# Lagopus_A_2.net
KiCad netlist of a schematic drawn in EAGLE
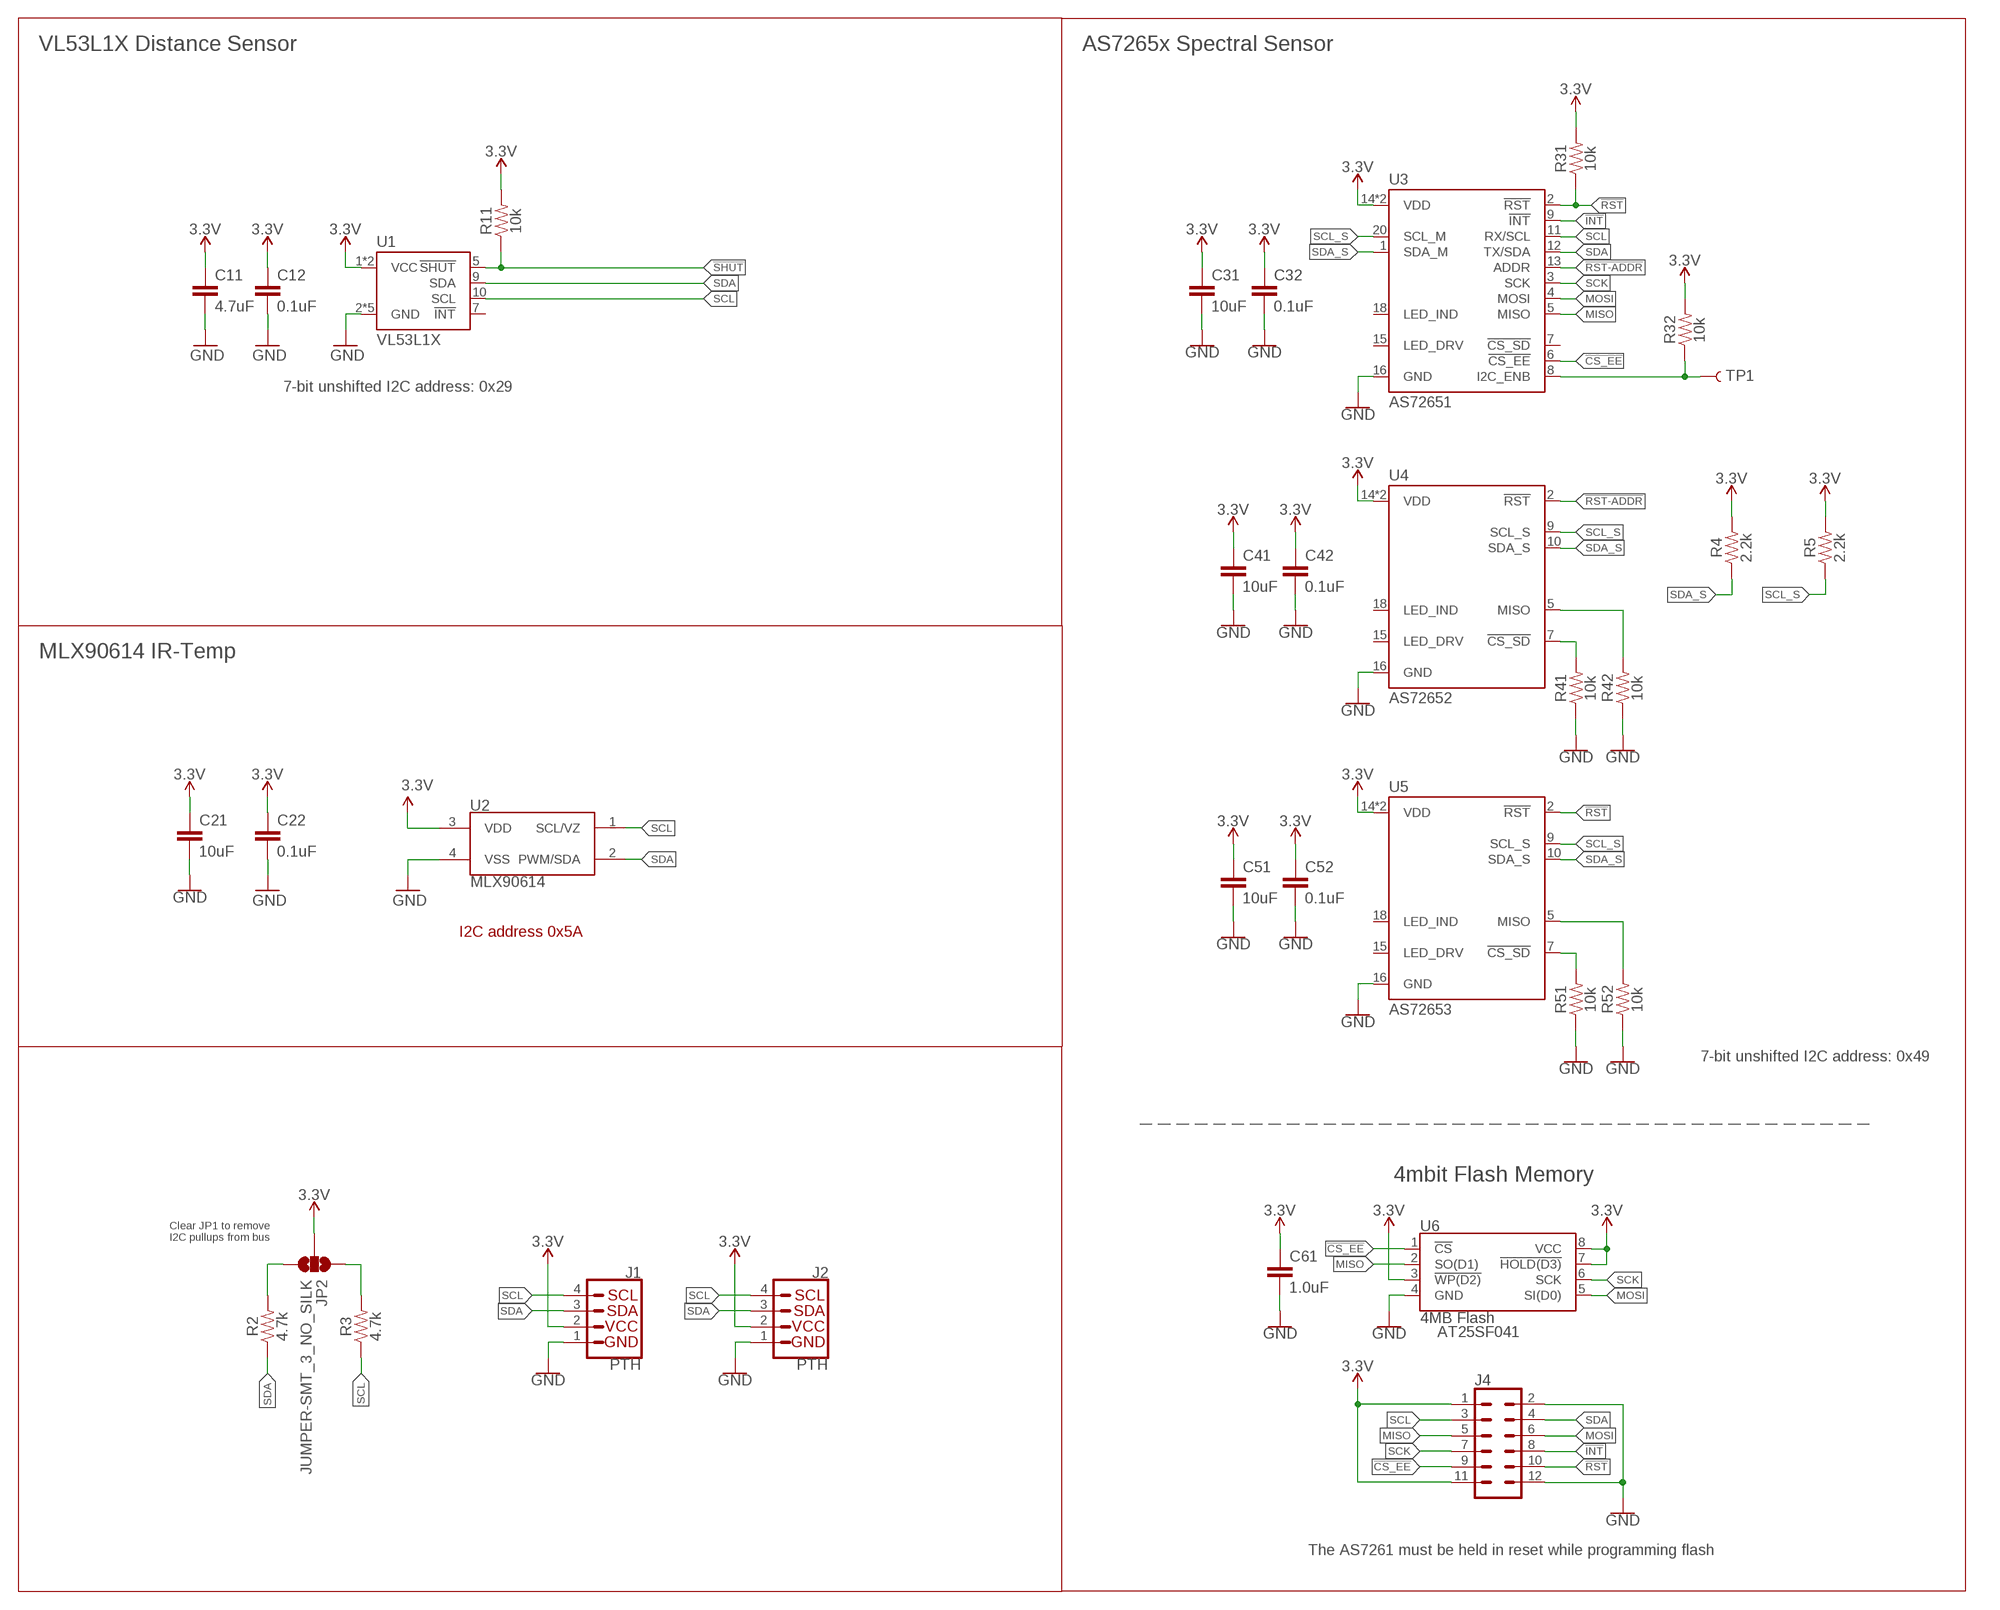
[diagram p0: schematic, sheet 1]

(export (version "E")
  (design (tool "Eeschema 10.0.6"))
  (components
    (comp (ref "C11")
      (value "4.7uF")
      (footprint "eagle-import:0603")
      (libsource (lib "eagle-import") (part "4.7UF0603"))
    )
    (comp (ref "C12")
      (value "0.1uF")
      (footprint "eagle-import:0603")
      (libsource (lib "eagle-import") (part "0.1UF-0603-25V-(+80/-20%)"))
    )
    (comp (ref "C21")
      (value "10uF")
      (footprint "eagle-import:0603")
      (libsource (lib "eagle-import") (part "10UF-0603-6.3V-20%"))
    )
    (comp (ref "C22")
      (value "0.1uF")
      (footprint "eagle-import:0603")
      (libsource (lib "eagle-import") (part "0.1UF-0603-25V-(+80/-20%)"))
    )
    (comp (ref "C31")
      (value "10uF")
      (footprint "eagle-import:0603")
      (libsource (lib "eagle-import") (part "10UF-0603-6.3V-20%"))
    )
    (comp (ref "C32")
      (value "0.1uF")
      (footprint "eagle-import:0603")
      (libsource (lib "eagle-import") (part "0.1UF-0603-25V-(+80/-20%)"))
    )
    (comp (ref "C41")
      (value "10uF")
      (footprint "eagle-import:0603")
      (libsource (lib "eagle-import") (part "10UF-0603-6.3V-20%"))
    )
    (comp (ref "C42")
      (value "0.1uF")
      (footprint "eagle-import:0603")
      (libsource (lib "eagle-import") (part "0.1UF-0603-25V-(+80/-20%)"))
    )
    (comp (ref "C51")
      (value "10uF")
      (footprint "eagle-import:0603")
      (libsource (lib "eagle-import") (part "10UF-0603-6.3V-20%"))
    )
    (comp (ref "C52")
      (value "0.1uF")
      (footprint "eagle-import:0603")
      (libsource (lib "eagle-import") (part "0.1UF-0603-25V-(+80/-20%)"))
    )
    (comp (ref "C61")
      (value "1.0uF")
      (footprint "eagle-import:0603")
      (libsource (lib "eagle-import") (part "1.0UF-0603-16V-10%"))
    )
    (comp (ref "J1")
      (value "PTH")
      (footprint "eagle-import:1X04_NO_SILK")
      (libsource (lib "eagle-import") (part "I2C_STANDARD_NO_SILK"))
    )
    (comp (ref "J2")
      (value "PTH")
      (footprint "eagle-import:1X04_NO_SILK")
      (libsource (lib "eagle-import") (part "I2C_STANDARD_NO_SILK"))
    )
    (comp (ref "J4")
      (value "CONN_06X2SMD_FEMALE")
      (footprint "eagle-import:2X6_SMD")
      (libsource (lib "eagle-import") (part "CONN_06X2SMD_FEMALE"))
    )
    (comp (ref "JP2")
      (value "JUMPER-SMT_3_NO_SILK")
      (footprint "eagle-import:SMT-JUMPER_3_NO_SILK")
      (libsource (lib "eagle-import") (part "JUMPER-SMT_3_NO_SILK"))
    )
    (comp (ref "R2")
      (value "4.7k")
      (footprint "eagle-import:0603")
      (libsource (lib "eagle-import") (part "4.7KOHM-0603-1/10W-1%"))
    )
    (comp (ref "R3")
      (value "4.7k")
      (footprint "eagle-import:0603")
      (libsource (lib "eagle-import") (part "4.7KOHM-0603-1/10W-1%"))
    )
    (comp (ref "R4")
      (value "2.2k")
      (footprint "eagle-import:0603")
      (libsource (lib "eagle-import") (part "2.2KOHM-0603-1/10W-1%"))
    )
    (comp (ref "R5")
      (value "2.2k")
      (footprint "eagle-import:0603")
      (libsource (lib "eagle-import") (part "2.2KOHM-0603-1/10W-1%"))
    )
    (comp (ref "R11")
      (value "10k")
      (footprint "eagle-import:0603")
      (libsource (lib "eagle-import") (part "10KOHM-0603-1/10W-1%"))
    )
    (comp (ref "R31")
      (value "10k")
      (footprint "eagle-import:0603")
      (libsource (lib "eagle-import") (part "10KOHM-0603-1/10W-1%"))
    )
    (comp (ref "R32")
      (value "10k")
      (footprint "eagle-import:0603")
      (libsource (lib "eagle-import") (part "10KOHM-0603-1/10W-1%"))
    )
    (comp (ref "R41")
      (value "10k")
      (footprint "eagle-import:0603")
      (libsource (lib "eagle-import") (part "10KOHM-0603-1/10W-1%"))
    )
    (comp (ref "R42")
      (value "10k")
      (footprint "eagle-import:0603")
      (libsource (lib "eagle-import") (part "10KOHM-0603-1/10W-1%"))
    )
    (comp (ref "R51")
      (value "10k")
      (footprint "eagle-import:0603")
      (libsource (lib "eagle-import") (part "10KOHM-0603-1/10W-1%"))
    )
    (comp (ref "R52")
      (value "10k")
      (footprint "eagle-import:0603")
      (libsource (lib "eagle-import") (part "10KOHM-0603-1/10W-1%"))
    )
    (comp (ref "TP1")
      (value "TEST-POINT3")
      (footprint "eagle-import:PAD.03X.03")
      (libsource (lib "eagle-import") (part "TEST-POINT3"))
    )
    (comp (ref "U1")
      (value "VL53L1X")
      (footprint "eagle-import:VL53L1X")
      (libsource (lib "eagle-import") (part "VL53L1XSMD"))
    )
    (comp (ref "U2")
      (value "MLX90614")
      (footprint "eagle-import:TO-39")
      (libsource (lib "eagle-import") (part "MLX90614"))
    )
    (comp (ref "U3")
      (value "AS72651")
      (footprint "eagle-import:LGA20")
      (libsource (lib "eagle-import") (part "AS72651"))
    )
    (comp (ref "U4")
      (value "AS72652")
      (footprint "eagle-import:LGA20")
      (libsource (lib "eagle-import") (part "AS72652"))
    )
    (comp (ref "U5")
      (value "AS72653")
      (footprint "eagle-import:LGA20")
      (libsource (lib "eagle-import") (part "AS72653"))
    )
    (comp (ref "U6")
      (value "4MB Flash")
      (footprint "eagle-import:SO08")
      (libsource (lib "eagle-import") (part "AT25SF041"))
    )
  )
  (nets
    (net (code "1") (name "/~{CS_EE}") (class "Default")
      (node (ref "J4") (pin "9") (pinfunction "9_9") (pintype "passive"))
      (node (ref "U3") (pin "6") (pinfunction "~{CS_EE}_6") (pintype "bidirectional"))
      (node (ref "U6") (pin "1") (pinfunction "~{CS}_1") (pintype "bidirectional"))
    )
    (net (code "2") (name "/~{INT}") (class "Default")
      (node (ref "J4") (pin "8") (pinfunction "8_8") (pintype "passive"))
      (node (ref "U3") (pin "9") (pinfunction "~{INT}_9") (pintype "bidirectional"))
    )
    (net (code "3") (name "/~{RST-ADDR}") (class "Default")
      (node (ref "U3") (pin "13") (pinfunction "ADDR_13") (pintype "bidirectional"))
      (node (ref "U4") (pin "2") (pinfunction "~{RST}_2") (pintype "bidirectional"))
    )
    (net (code "4") (name "/~{RST}") (class "Default")
      (node (ref "J4") (pin "10") (pinfunction "10_10") (pintype "passive"))
      (node (ref "R31") (pin "1") (pinfunction "1_1") (pintype "passive"))
      (node (ref "U3") (pin "2") (pinfunction "~{RST}_2") (pintype "bidirectional"))
      (node (ref "U5") (pin "2") (pinfunction "~{RST}_2") (pintype "bidirectional"))
    )
    (net (code "5") (name "/~{SHUT}") (class "Default")
      (node (ref "R11") (pin "1") (pinfunction "1_1") (pintype "passive"))
      (node (ref "U1") (pin "5") (pinfunction "~{SHUT}_5") (pintype "bidirectional"))
    )
    (net (code "6") (name "3.3V") (class "Default")
      (node (ref "C11") (pin "1") (pinfunction "1_1") (pintype "passive"))
      (node (ref "C12") (pin "1") (pinfunction "1_1") (pintype "passive"))
      (node (ref "C21") (pin "1") (pinfunction "1_1") (pintype "passive"))
      (node (ref "C22") (pin "1") (pinfunction "1_1") (pintype "passive"))
      (node (ref "C31") (pin "1") (pinfunction "1_1") (pintype "passive"))
      (node (ref "C32") (pin "1") (pinfunction "1_1") (pintype "passive"))
      (node (ref "C41") (pin "1") (pinfunction "1_1") (pintype "passive"))
      (node (ref "C42") (pin "1") (pinfunction "1_1") (pintype "passive"))
      (node (ref "C51") (pin "1") (pinfunction "1_1") (pintype "passive"))
      (node (ref "C52") (pin "1") (pinfunction "1_1") (pintype "passive"))
      (node (ref "C61") (pin "1") (pinfunction "1_1") (pintype "passive"))
      (node (ref "J1") (pin "2") (pinfunction "VCC_2") (pintype "power_in"))
      (node (ref "J2") (pin "2") (pinfunction "VCC_2") (pintype "power_in"))
      (node (ref "J4") (pin "1") (pinfunction "1_1") (pintype "passive"))
      (node (ref "J4") (pin "11") (pinfunction "11_11") (pintype "passive"))
      (node (ref "JP2") (pin "2") (pinfunction "2_2") (pintype "passive"))
      (node (ref "R11") (pin "2") (pinfunction "2_2") (pintype "passive"))
      (node (ref "R31") (pin "2") (pinfunction "2_2") (pintype "passive"))
      (node (ref "R32") (pin "2") (pinfunction "2_2") (pintype "passive"))
      (node (ref "R4") (pin "2") (pinfunction "2_2") (pintype "passive"))
      (node (ref "R5") (pin "2") (pinfunction "2_2") (pintype "passive"))
      (node (ref "U1") (pin "1") (pinfunction "VCC_1") (pintype "bidirectional"))
      (node (ref "U1") (pin "11") (pinfunction "VCC_11") (pintype "bidirectional"))
      (node (ref "U2") (pin "3") (pinfunction "VDD_3") (pintype "bidirectional"))
      (node (ref "U3") (pin "14") (pinfunction "VDD_14") (pintype "bidirectional"))
      (node (ref "U3") (pin "17") (pinfunction "VDD_17") (pintype "bidirectional"))
      (node (ref "U4") (pin "14") (pinfunction "VDD_14") (pintype "bidirectional"))
      (node (ref "U4") (pin "17") (pinfunction "VDD_17") (pintype "bidirectional"))
      (node (ref "U5") (pin "14") (pinfunction "VDD_14") (pintype "bidirectional"))
      (node (ref "U5") (pin "17") (pinfunction "VDD_17") (pintype "bidirectional"))
      (node (ref "U6") (pin "3") (pinfunction "~{WP(D2})_3") (pintype "bidirectional"))
      (node (ref "U6") (pin "7") (pinfunction "~{HOLD(D3})_7") (pintype "bidirectional"))
      (node (ref "U6") (pin "8") (pinfunction "VCC_8") (pintype "bidirectional"))
    )
    (net (code "7") (name "GND") (class "Default")
      (node (ref "C11") (pin "2") (pinfunction "2_2") (pintype "passive"))
      (node (ref "C12") (pin "2") (pinfunction "2_2") (pintype "passive"))
      (node (ref "C21") (pin "2") (pinfunction "2_2") (pintype "passive"))
      (node (ref "C22") (pin "2") (pinfunction "2_2") (pintype "passive"))
      (node (ref "C31") (pin "2") (pinfunction "2_2") (pintype "passive"))
      (node (ref "C32") (pin "2") (pinfunction "2_2") (pintype "passive"))
      (node (ref "C41") (pin "2") (pinfunction "2_2") (pintype "passive"))
      (node (ref "C42") (pin "2") (pinfunction "2_2") (pintype "passive"))
      (node (ref "C51") (pin "2") (pinfunction "2_2") (pintype "passive"))
      (node (ref "C52") (pin "2") (pinfunction "2_2") (pintype "passive"))
      (node (ref "C61") (pin "2") (pinfunction "2_2") (pintype "passive"))
      (node (ref "J1") (pin "1") (pinfunction "GND_1") (pintype "power_in"))
      (node (ref "J2") (pin "1") (pinfunction "GND_1") (pintype "power_in"))
      (node (ref "J4") (pin "12") (pinfunction "12_12") (pintype "passive"))
      (node (ref "J4") (pin "2") (pinfunction "2_2") (pintype "passive"))
      (node (ref "R41") (pin "1") (pinfunction "1_1") (pintype "passive"))
      (node (ref "R42") (pin "1") (pinfunction "1_1") (pintype "passive"))
      (node (ref "R51") (pin "1") (pinfunction "1_1") (pintype "passive"))
      (node (ref "R52") (pin "1") (pinfunction "1_1") (pintype "passive"))
      (node (ref "U1") (pin "12") (pinfunction "GND_12") (pintype "bidirectional"))
      (node (ref "U1") (pin "2") (pinfunction "GND_2") (pintype "bidirectional"))
      (node (ref "U1") (pin "3") (pinfunction "GND_3") (pintype "bidirectional"))
      (node (ref "U1") (pin "4") (pinfunction "GND_4") (pintype "bidirectional"))
      (node (ref "U1") (pin "6") (pinfunction "GND_6") (pintype "bidirectional"))
      (node (ref "U2") (pin "4") (pinfunction "VSS_4") (pintype "bidirectional"))
      (node (ref "U3") (pin "16") (pinfunction "GND_16") (pintype "bidirectional"))
      (node (ref "U4") (pin "16") (pinfunction "GND_16") (pintype "bidirectional"))
      (node (ref "U5") (pin "16") (pinfunction "GND_16") (pintype "bidirectional"))
      (node (ref "U6") (pin "4") (pinfunction "GND_4") (pintype "bidirectional"))
    )
    (net (code "8") (name "MISO") (class "Default")
      (node (ref "J4") (pin "5") (pinfunction "5_5") (pintype "passive"))
      (node (ref "U3") (pin "5") (pinfunction "MISO_5") (pintype "bidirectional"))
      (node (ref "U6") (pin "2") (pinfunction "SO(D1)_2") (pintype "bidirectional"))
    )
    (net (code "9") (name "MOSI") (class "Default")
      (node (ref "J4") (pin "6") (pinfunction "6_6") (pintype "passive"))
      (node (ref "U3") (pin "4") (pinfunction "MOSI_4") (pintype "bidirectional"))
      (node (ref "U6") (pin "5") (pinfunction "SI(D0)_5") (pintype "bidirectional"))
    )
    (net (code "10") (name "Net-(JP2-Pad1)") (class "Default")
      (node (ref "JP2") (pin "1") (pinfunction "1_1") (pintype "passive"))
      (node (ref "R3") (pin "2") (pinfunction "2_2") (pintype "passive"))
    )
    (net (code "11") (name "Net-(JP2-Pad3)") (class "Default")
      (node (ref "JP2") (pin "3") (pinfunction "3_3") (pintype "passive"))
      (node (ref "R2") (pin "2") (pinfunction "2_2") (pintype "passive"))
    )
    (net (code "12") (name "Net-(TP1-1)") (class "Default")
      (node (ref "R32") (pin "1") (pinfunction "1_1") (pintype "passive"))
      (node (ref "TP1") (pin "P$1") (pinfunction "1_P$1") (pintype "bidirectional"))
      (node (ref "U3") (pin "8") (pinfunction "I2C_ENB_8") (pintype "bidirectional"))
    )
    (net (code "13") (name "Net-(U4-MISO)") (class "Default")
      (node (ref "R42") (pin "2") (pinfunction "2_2") (pintype "passive"))
      (node (ref "U4") (pin "5") (pinfunction "MISO_5") (pintype "bidirectional"))
    )
    (net (code "14") (name "Net-(U4-~{CS_SD})") (class "Default")
      (node (ref "R41") (pin "2") (pinfunction "2_2") (pintype "passive"))
      (node (ref "U4") (pin "7") (pinfunction "~{CS_SD}_7") (pintype "bidirectional"))
    )
    (net (code "15") (name "Net-(U5-MISO)") (class "Default")
      (node (ref "R52") (pin "2") (pinfunction "2_2") (pintype "passive"))
      (node (ref "U5") (pin "5") (pinfunction "MISO_5") (pintype "bidirectional"))
    )
    (net (code "16") (name "Net-(U5-~{CS_SD})") (class "Default")
      (node (ref "R51") (pin "2") (pinfunction "2_2") (pintype "passive"))
      (node (ref "U5") (pin "7") (pinfunction "~{CS_SD}_7") (pintype "bidirectional"))
    )
    (net (code "17") (name "SCK") (class "Default")
      (node (ref "J4") (pin "7") (pinfunction "7_7") (pintype "passive"))
      (node (ref "U3") (pin "3") (pinfunction "SCK_3") (pintype "bidirectional"))
      (node (ref "U6") (pin "6") (pinfunction "SCK_6") (pintype "bidirectional"))
    )
    (net (code "18") (name "SCL") (class "Default")
      (node (ref "J1") (pin "4") (pinfunction "SCL_4") (pintype "passive"))
      (node (ref "J2") (pin "4") (pinfunction "SCL_4") (pintype "passive"))
      (node (ref "J4") (pin "3") (pinfunction "3_3") (pintype "passive"))
      (node (ref "R3") (pin "1") (pinfunction "1_1") (pintype "passive"))
      (node (ref "U1") (pin "10") (pinfunction "SCL_10") (pintype "bidirectional"))
      (node (ref "U2") (pin "1") (pinfunction "SCL/VZ_1") (pintype "bidirectional"))
      (node (ref "U3") (pin "11") (pinfunction "RX/SCL_11") (pintype "bidirectional"))
    )
    (net (code "19") (name "SCL_S") (class "Default")
      (node (ref "R5") (pin "1") (pinfunction "1_1") (pintype "passive"))
      (node (ref "U3") (pin "20") (pinfunction "SCL_M_20") (pintype "bidirectional"))
      (node (ref "U4") (pin "9") (pinfunction "SCL_S_9") (pintype "bidirectional"))
      (node (ref "U5") (pin "9") (pinfunction "SCL_S_9") (pintype "bidirectional"))
    )
    (net (code "20") (name "SDA") (class "Default")
      (node (ref "J1") (pin "3") (pinfunction "SDA_3") (pintype "passive"))
      (node (ref "J2") (pin "3") (pinfunction "SDA_3") (pintype "passive"))
      (node (ref "J4") (pin "4") (pinfunction "4_4") (pintype "passive"))
      (node (ref "R2") (pin "1") (pinfunction "1_1") (pintype "passive"))
      (node (ref "U1") (pin "9") (pinfunction "SDA_9") (pintype "bidirectional"))
      (node (ref "U2") (pin "2") (pinfunction "PWM/SDA_2") (pintype "bidirectional"))
      (node (ref "U3") (pin "12") (pinfunction "TX/SDA_12") (pintype "bidirectional"))
    )
    (net (code "21") (name "SDA_S") (class "Default")
      (node (ref "R4") (pin "1") (pinfunction "1_1") (pintype "passive"))
      (node (ref "U3") (pin "1") (pinfunction "SDA_M_1") (pintype "bidirectional"))
      (node (ref "U4") (pin "10") (pinfunction "SDA_S_10") (pintype "bidirectional"))
      (node (ref "U5") (pin "10") (pinfunction "SDA_S_10") (pintype "bidirectional"))
    )
    (net (code "22") (name "unconnected-(U1-~{INT}-Pad7)") (class "Default")
      (node (ref "U1") (pin "7") (pinfunction "~{INT}_7") (pintype "bidirectional"))
    )
    (net (code "23") (name "unconnected-(U3-LED_DRV-Pad15)") (class "Default")
      (node (ref "U3") (pin "15") (pinfunction "LED_DRV_15") (pintype "bidirectional"))
    )
    (net (code "24") (name "unconnected-(U3-LED_IND-Pad18)") (class "Default")
      (node (ref "U3") (pin "18") (pinfunction "LED_IND_18") (pintype "bidirectional"))
    )
    (net (code "25") (name "unconnected-(U3-~{CS_SD}-Pad7)") (class "Default")
      (node (ref "U3") (pin "7") (pinfunction "~{CS_SD}_7") (pintype "bidirectional"))
    )
    (net (code "26") (name "unconnected-(U4-LED_DRV-Pad15)") (class "Default")
      (node (ref "U4") (pin "15") (pinfunction "LED_DRV_15") (pintype "bidirectional"))
    )
    (net (code "27") (name "unconnected-(U4-LED_IND-Pad18)") (class "Default")
      (node (ref "U4") (pin "18") (pinfunction "LED_IND_18") (pintype "bidirectional"))
    )
    (net (code "28") (name "unconnected-(U5-LED_DRV-Pad15)") (class "Default")
      (node (ref "U5") (pin "15") (pinfunction "LED_DRV_15") (pintype "bidirectional"))
    )
    (net (code "29") (name "unconnected-(U5-LED_IND-Pad18)") (class "Default")
      (node (ref "U5") (pin "18") (pinfunction "LED_IND_18") (pintype "bidirectional"))
    )
  )
)
